# power-distribution.net
KiCad netlist of a schematic drawn in EAGLE
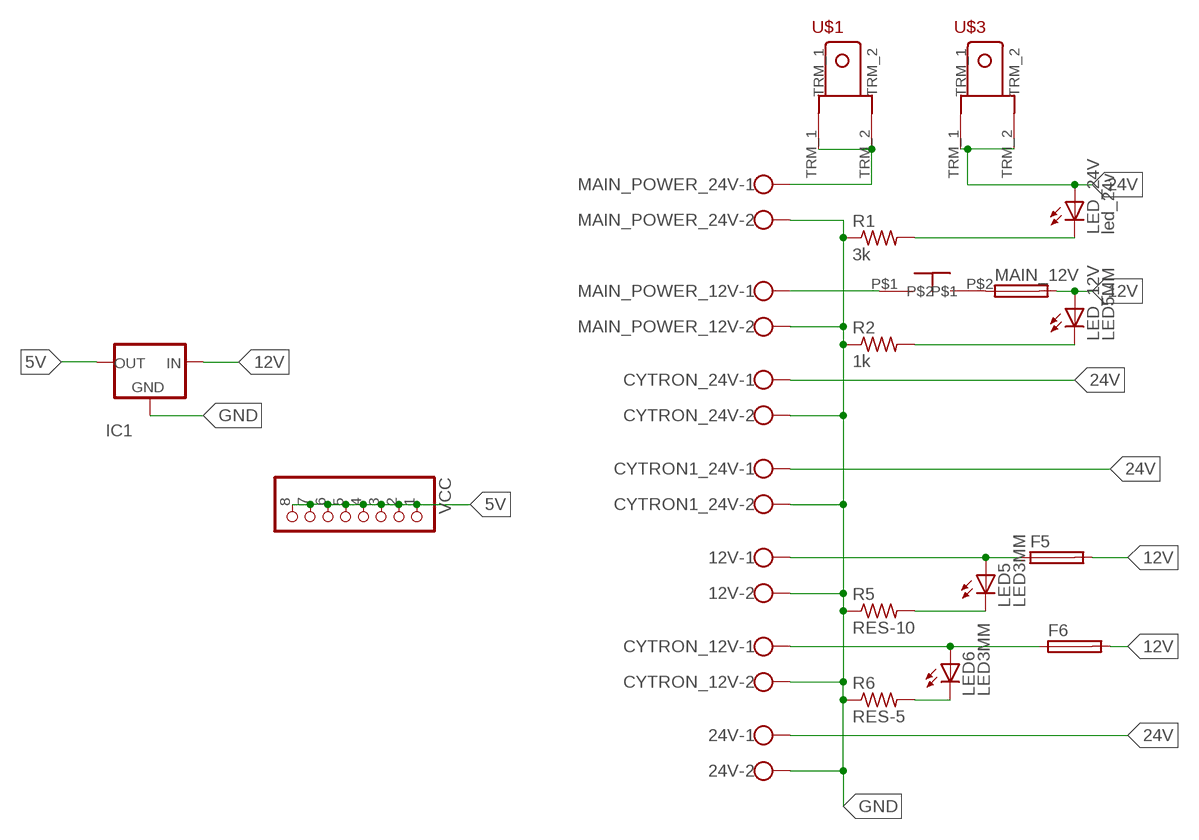
[diagram p0: schematic, sheet 1]

(export (version "E")
  (design (tool "Eeschema 10.0.6"))
  (components
    (comp (ref "12V")
      (value "ROSTA.POWER")
      (footprint "eagle-import:W239-302")
      (libsource (lib "eagle-import") (part "ROSTA.POWER"))
    )
    (comp (ref "24V")
      (value "ROSTA.POWER")
      (footprint "eagle-import:W239-302")
      (libsource (lib "eagle-import") (part "ROSTA.POWER"))
    )
    (comp (ref "CYTRON1_24V")
      (value "ROSTA.POWER")
      (footprint "eagle-import:W239-302")
      (libsource (lib "eagle-import") (part "ROSTA.POWER"))
    )
    (comp (ref "CYTRON_12V")
      (value "ROSTA.POWER")
      (footprint "eagle-import:W239-302")
      (libsource (lib "eagle-import") (part "ROSTA.POWER"))
    )
    (comp (ref "CYTRON_24V")
      (value "ROSTA.POWER")
      (footprint "eagle-import:W239-302")
      (libsource (lib "eagle-import") (part "ROSTA.POWER"))
    )
    (comp (ref "F5")
      (value "FUSE_HOLDER")
      (footprint "eagle-import:SH22,5A")
      (libsource (lib "eagle-import") (part "FUSE_HOLDER"))
    )
    (comp (ref "F6")
      (value "FUSE_HOLDER")
      (footprint "eagle-import:SH22,5A")
      (libsource (lib "eagle-import") (part "FUSE_HOLDER"))
    )
    (comp (ref "IC1")
      (value "78XX-METAL")
      (footprint "eagle-import:TO3-79")
      (libsource (lib "eagle-import") (part "78XX-METAL"))
    )
    (comp (ref "LED5")
      (value "LED3MM")
      (footprint "eagle-import:LED3MM")
      (libsource (lib "eagle-import") (part "LED3MM"))
    )
    (comp (ref "LED6")
      (value "LED3MM")
      (footprint "eagle-import:LED3MM")
      (libsource (lib "eagle-import") (part "LED3MM"))
    )
    (comp (ref "LED_12V")
      (value "LED5MM")
      (footprint "eagle-import:LED5MM")
      (libsource (lib "eagle-import") (part "LED5MM"))
    )
    (comp (ref "LED_24V")
      (value "led_24v")
      (footprint "eagle-import:LED5MM")
      (libsource (lib "eagle-import") (part "LED5MM"))
    )
    (comp (ref "MAIN_12V")
      (value "FUSE_HOLDER")
      (footprint "eagle-import:SH22,5A")
      (libsource (lib "eagle-import") (part "FUSE_HOLDER"))
    )
    (comp (ref "MAIN_POWER_12V")
      (value "ROSTA.POWER")
      (footprint "eagle-import:W239-302")
      (libsource (lib "eagle-import") (part "ROSTA.POWER"))
    )
    (comp (ref "MAIN_POWER_24V")
      (value "ROSTA.POWER")
      (footprint "eagle-import:W239-302")
      (libsource (lib "eagle-import") (part "ROSTA.POWER"))
    )
    (comp (ref "R1")
      (value "3k")
      (footprint "eagle-import:0204_5")
      (libsource (lib "eagle-import") (part "RES-5"))
    )
    (comp (ref "R2")
      (value "1k")
      (footprint "eagle-import:0207_12")
      (libsource (lib "eagle-import") (part "RES-12"))
    )
    (comp (ref "R5")
      (value "RES-10")
      (footprint "eagle-import:0207_10")
      (libsource (lib "eagle-import") (part "RES-10"))
    )
    (comp (ref "R6")
      (value "RES-5")
      (footprint "eagle-import:0204_5")
      (libsource (lib "eagle-import") (part "RES-5"))
    )
    (comp (ref "U$1")
      (value "TERMINAL_EDITED")
      (footprint "eagle-import:TERMINAL_EDITED")
      (libsource (lib "eagle-import") (part "TERMINAL_EDITED"))
    )
    (comp (ref "U$2")
      (value "SWITCH_2")
      (footprint "eagle-import:ON_OFF")
      (libsource (lib "eagle-import") (part "SWITCH_2"))
    )
    (comp (ref "U$3")
      (value "TERMINAL_EDITED")
      (footprint "eagle-import:TERMINAL_EDITED")
      (libsource (lib "eagle-import") (part "TERMINAL_EDITED"))
    )
    (comp (ref "VCC")
      (value "PINHD-1X8")
      (footprint "eagle-import:1X08")
      (libsource (lib "eagle-import") (part "PINHD-1X8"))
    )
  )
  (nets
    (net (code "1") (name "5V") (class "Default")
      (node (ref "IC1") (pin "1") (pinfunction "OUT_1") (pintype "passive"))
      (node (ref "VCC") (pin "1") (pinfunction "1_1") (pintype "passive"))
      (node (ref "VCC") (pin "2") (pinfunction "2_2") (pintype "passive"))
      (node (ref "VCC") (pin "3") (pinfunction "3_3") (pintype "passive"))
      (node (ref "VCC") (pin "4") (pinfunction "4_4") (pintype "passive"))
      (node (ref "VCC") (pin "5") (pinfunction "5_5") (pintype "passive"))
      (node (ref "VCC") (pin "6") (pinfunction "6_6") (pintype "passive"))
      (node (ref "VCC") (pin "7") (pinfunction "7_7") (pintype "passive"))
      (node (ref "VCC") (pin "8") (pinfunction "8_8") (pintype "passive"))
    )
    (net (code "2") (name "12V") (class "Default")
      (node (ref "F5") (pin "2") (pinfunction "2_2") (pintype "passive"))
      (node (ref "F6") (pin "2") (pinfunction "2_2") (pintype "passive"))
      (node (ref "IC1") (pin "3") (pinfunction "IN_3") (pintype "input"))
      (node (ref "LED_12V") (pin "A") (pinfunction "A_A") (pintype "passive"))
      (node (ref "MAIN_12V") (pin "2") (pinfunction "2_2") (pintype "passive"))
    )
    (net (code "3") (name "24V") (class "Default")
      (node (ref "24V") (pin "1") (pinfunction "KL_1") (pintype "passive"))
      (node (ref "CYTRON1_24V") (pin "1") (pinfunction "KL_1") (pintype "passive"))
      (node (ref "CYTRON_24V") (pin "1") (pinfunction "KL_1") (pintype "passive"))
      (node (ref "LED_24V") (pin "A") (pinfunction "A_A") (pintype "passive"))
      (node (ref "U$3") (pin "TRM_1") (pinfunction "TRM_1_TRM_1") (pintype "bidirectional"))
      (node (ref "U$3") (pin "TRM_2") (pinfunction "TRM_2_TRM_2") (pintype "bidirectional"))
    )
    (net (code "4") (name "GND") (class "Default")
      (node (ref "12V") (pin "2") (pinfunction "KL_2") (pintype "passive"))
      (node (ref "24V") (pin "2") (pinfunction "KL_2") (pintype "passive"))
      (node (ref "CYTRON1_24V") (pin "2") (pinfunction "KL_2") (pintype "passive"))
      (node (ref "CYTRON_12V") (pin "2") (pinfunction "KL_2") (pintype "passive"))
      (node (ref "CYTRON_24V") (pin "2") (pinfunction "KL_2") (pintype "passive"))
      (node (ref "IC1") (pin "2") (pinfunction "GND_2") (pintype "input"))
      (node (ref "MAIN_POWER_12V") (pin "2") (pinfunction "KL_2") (pintype "passive"))
      (node (ref "MAIN_POWER_24V") (pin "2") (pinfunction "KL_2") (pintype "passive"))
      (node (ref "R1") (pin "1") (pinfunction "1_1") (pintype "passive"))
      (node (ref "R2") (pin "1") (pinfunction "1_1") (pintype "passive"))
      (node (ref "R5") (pin "1") (pinfunction "1_1") (pintype "passive"))
      (node (ref "R6") (pin "1") (pinfunction "1_1") (pintype "passive"))
    )
    (net (code "5") (name "Net-(12VA-KL)") (class "Default")
      (node (ref "12V") (pin "1") (pinfunction "KL_1") (pintype "passive"))
      (node (ref "F5") (pin "1") (pinfunction "1_1") (pintype "passive"))
      (node (ref "LED5") (pin "A") (pinfunction "A_A") (pintype "passive"))
    )
    (net (code "6") (name "Net-(CYTRON_12VA-KL)") (class "Default")
      (node (ref "CYTRON_12V") (pin "1") (pinfunction "KL_1") (pintype "passive"))
      (node (ref "F6") (pin "1") (pinfunction "1_1") (pintype "passive"))
      (node (ref "LED6") (pin "A") (pinfunction "A_A") (pintype "passive"))
    )
    (net (code "7") (name "Net-(LED5-C)") (class "Default")
      (node (ref "LED5") (pin "K") (pinfunction "C_K") (pintype "passive"))
      (node (ref "R5") (pin "2") (pinfunction "2_2") (pintype "passive"))
    )
    (net (code "8") (name "Net-(LED6-C)") (class "Default")
      (node (ref "LED6") (pin "K") (pinfunction "C_K") (pintype "passive"))
      (node (ref "R6") (pin "2") (pinfunction "2_2") (pintype "passive"))
    )
    (net (code "9") (name "Net-(LED_12V-C)") (class "Default")
      (node (ref "LED_12V") (pin "K") (pinfunction "C_K") (pintype "passive"))
      (node (ref "R2") (pin "2") (pinfunction "2_2") (pintype "passive"))
    )
    (net (code "10") (name "Net-(LED_24V-C)") (class "Default")
      (node (ref "LED_24V") (pin "K") (pinfunction "C_K") (pintype "passive"))
      (node (ref "R1") (pin "2") (pinfunction "2_2") (pintype "passive"))
    )
    (net (code "11") (name "Net-(MAIN_12V-Pad1)") (class "Default")
      (node (ref "MAIN_12V") (pin "1") (pinfunction "1_1") (pintype "passive"))
      (node (ref "U$2") (pin "P$2") (pinfunction "P$2_P$2") (pintype "bidirectional"))
    )
    (net (code "12") (name "Net-(MAIN_POWER_12VA-KL)") (class "Default")
      (node (ref "MAIN_POWER_12V") (pin "1") (pinfunction "KL_1") (pintype "passive"))
      (node (ref "U$2") (pin "P$1") (pinfunction "P$1_P$1") (pintype "bidirectional"))
    )
    (net (code "13") (name "Net-(MAIN_POWER_24VA-KL)") (class "Default")
      (node (ref "MAIN_POWER_24V") (pin "1") (pinfunction "KL_1") (pintype "passive"))
      (node (ref "U$1") (pin "TRM_1") (pinfunction "TRM_1_TRM_1") (pintype "bidirectional"))
      (node (ref "U$1") (pin "TRM_2") (pinfunction "TRM_2_TRM_2") (pintype "bidirectional"))
    )
  )
)
